# MainCircuit.net
KiCad netlist of a schematic drawn in Altium Designer
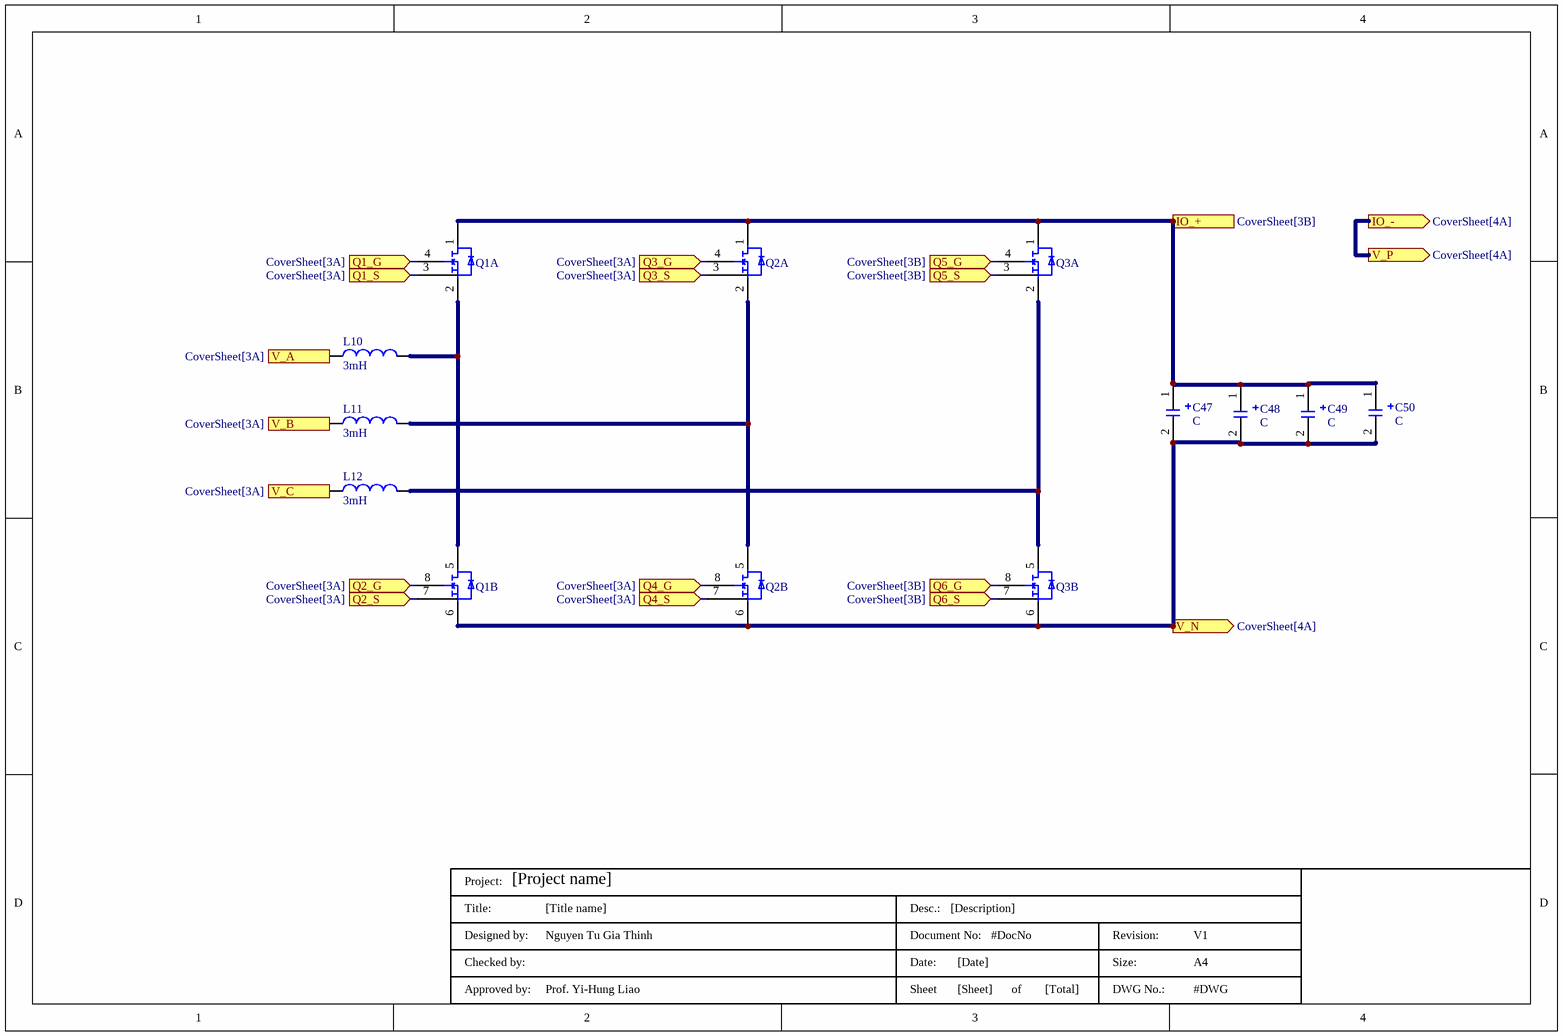
[diagram p0: MainCircuit.SchDoc]

(export (version "E")
  (design (tool "Eeschema 10.0.6"))
  (components
    (comp (ref "C47") (value "C") (footprint "CAPACITOR") (libsource (lib "ViennaRectifier") (part "C")))
    (comp (ref "C48") (value "C") (footprint "CAPACITOR") (libsource (lib "ViennaRectifier") (part "C")))
    (comp (ref "C49") (value "C") (footprint "CAPACITOR") (libsource (lib "ViennaRectifier") (part "C")))
    (comp (ref "C50") (value "C") (footprint "CAPACITOR") (libsource (lib "ViennaRectifier") (part "C")))
    (comp (ref "L10")
      (value "3mH")
      (footprint "CS467125x2")
      (description "Inductor Powder core CS467125 x2 cores, phi 1.6mm, 1 layer, 74 turns, 3mH.")
      (fields (field (name "Comment") "Inductor"))
      (libsource (lib "ViennaRectifier") (part "CS467125x2"))
    )
    (comp (ref "L11")
      (value "3mH")
      (footprint "CS467125x2")
      (description "Inductor Powder core CS467125 x2 cores, phi 1.6mm, 1 layer, 74 turns, 3mH.")
      (fields (field (name "Comment") "Inductor"))
      (libsource (lib "ViennaRectifier") (part "CS467125x2"))
    )
    (comp (ref "L12")
      (value "3mH")
      (footprint "CS467125x2")
      (description "Inductor Powder core CS467125 x2 cores, phi 1.6mm, 1 layer, 74 turns, 3mH.")
      (fields (field (name "Comment") "Inductor"))
      (libsource (lib "ViennaRectifier") (part "CS467125x2"))
    )
    (comp (ref "Q1")
      (value "SiC MOS")
      (footprint "C247-050-2VE")
      (description "MOSFETs, N-Channel 1200 V 100A (Tc) 431W (Tc) Through Hole TO-247-4L(X)")
      (libsource (lib "ViennaRectifier") (part "C247-050-2VE"))
    )
    (comp (ref "Q2")
      (value "SiC MOS")
      (footprint "C247-050-2VE")
      (description "MOSFETs, N-Channel 1200 V 100A (Tc) 431W (Tc) Through Hole TO-247-4L(X)")
      (libsource (lib "ViennaRectifier") (part "C247-050-2VE"))
    )
    (comp (ref "Q3")
      (value "SiC MOS")
      (footprint "C247-050-2VE")
      (description "MOSFETs, N-Channel 1200 V 100A (Tc) 431W (Tc) Through Hole TO-247-4L(X)")
      (libsource (lib "ViennaRectifier") (part "C247-050-2VE"))
    )
  )
  (nets
    (net (code "1") (name "/IO_+") (class "Default")
      (node (ref "C47") (pin "1") (pinfunction "+_1") (pintype "passive"))
      (node (ref "C48") (pin "1") (pinfunction "+_1") (pintype "passive"))
      (node (ref "C49") (pin "1") (pinfunction "+_1") (pintype "passive"))
      (node (ref "C50") (pin "1") (pinfunction "+_1") (pintype "passive"))
      (node (ref "Q1") (pin "1") (pinfunction "D_1") (pintype "passive"))
      (node (ref "Q2") (pin "1") (pinfunction "D_1") (pintype "passive"))
      (node (ref "Q3") (pin "1") (pinfunction "D_1") (pintype "passive"))
    )
    (net (code "3") (name "/Q1_G") (class "Default")
      (node (ref "Q1") (pin "4") (pinfunction "G_4") (pintype "passive"))
    )
    (net (code "4") (name "/Q1_S") (class "Default")
      (node (ref "Q1") (pin "3") (pinfunction "S2_3") (pintype "passive"))
    )
    (net (code "5") (name "/Q2_G") (class "Default")
      (node (ref "Q1") (pin "8") (pinfunction "G_8") (pintype "passive"))
    )
    (net (code "6") (name "/Q2_S") (class "Default")
      (node (ref "Q1") (pin "7") (pinfunction "S2_7") (pintype "passive"))
    )
    (net (code "7") (name "/Q3_G") (class "Default")
      (node (ref "Q2") (pin "4") (pinfunction "G_4") (pintype "passive"))
    )
    (net (code "8") (name "/Q3_S") (class "Default")
      (node (ref "Q2") (pin "3") (pinfunction "S2_3") (pintype "passive"))
    )
    (net (code "9") (name "/Q4_G") (class "Default")
      (node (ref "Q2") (pin "8") (pinfunction "G_8") (pintype "passive"))
    )
    (net (code "10") (name "/Q4_S") (class "Default")
      (node (ref "Q2") (pin "7") (pinfunction "S2_7") (pintype "passive"))
    )
    (net (code "11") (name "/Q5_G") (class "Default")
      (node (ref "Q3") (pin "4") (pinfunction "G_4") (pintype "passive"))
    )
    (net (code "12") (name "/Q5_S") (class "Default")
      (node (ref "Q3") (pin "3") (pinfunction "S2_3") (pintype "passive"))
    )
    (net (code "13") (name "/Q6_G") (class "Default")
      (node (ref "Q3") (pin "8") (pinfunction "G_8") (pintype "passive"))
    )
    (net (code "14") (name "/Q6_S") (class "Default")
      (node (ref "Q3") (pin "7") (pinfunction "S2_7") (pintype "passive"))
    )
    (net (code "15") (name "/V_A") (class "Default")
      (node (ref "L10") (pin "1") (pinfunction "1_1") (pintype "passive"))
    )
    (net (code "16") (name "/V_B") (class "Default")
      (node (ref "L11") (pin "1") (pinfunction "1_1") (pintype "passive"))
    )
    (net (code "17") (name "/V_C") (class "Default")
      (node (ref "L12") (pin "1") (pinfunction "1_1") (pintype "passive"))
    )
    (net (code "18") (name "/V_N") (class "Default")
      (node (ref "C47") (pin "2") (pinfunction "-_2") (pintype "passive"))
      (node (ref "C48") (pin "2") (pinfunction "-_2") (pintype "passive"))
      (node (ref "C49") (pin "2") (pinfunction "-_2") (pintype "passive"))
      (node (ref "C50") (pin "2") (pinfunction "-_2") (pintype "passive"))
      (node (ref "Q1") (pin "6") (pinfunction "S1_6") (pintype "passive"))
      (node (ref "Q2") (pin "6") (pinfunction "S1_6") (pintype "passive"))
      (node (ref "Q3") (pin "6") (pinfunction "S1_6") (pintype "passive"))
    )
    (net (code "19") (name "Net-(Q1A-S1)") (class "Default")
      (node (ref "L10") (pin "2") (pinfunction "2_2") (pintype "passive"))
      (node (ref "Q1") (pin "2") (pinfunction "S1_2") (pintype "passive"))
      (node (ref "Q1") (pin "5") (pinfunction "D_5") (pintype "passive"))
    )
    (net (code "20") (name "Net-(Q2A-S1)") (class "Default")
      (node (ref "L11") (pin "2") (pinfunction "2_2") (pintype "passive"))
      (node (ref "Q2") (pin "2") (pinfunction "S1_2") (pintype "passive"))
      (node (ref "Q2") (pin "5") (pinfunction "D_5") (pintype "passive"))
    )
    (net (code "21") (name "Net-(Q3A-S1)") (class "Default")
      (node (ref "L12") (pin "2") (pinfunction "2_2") (pintype "passive"))
      (node (ref "Q3") (pin "2") (pinfunction "S1_2") (pintype "passive"))
      (node (ref "Q3") (pin "5") (pinfunction "D_5") (pintype "passive"))
    )
  )
)
